# 04-multimodal-flash.net
KiCad netlist of a schematic drawn in Altium Designer
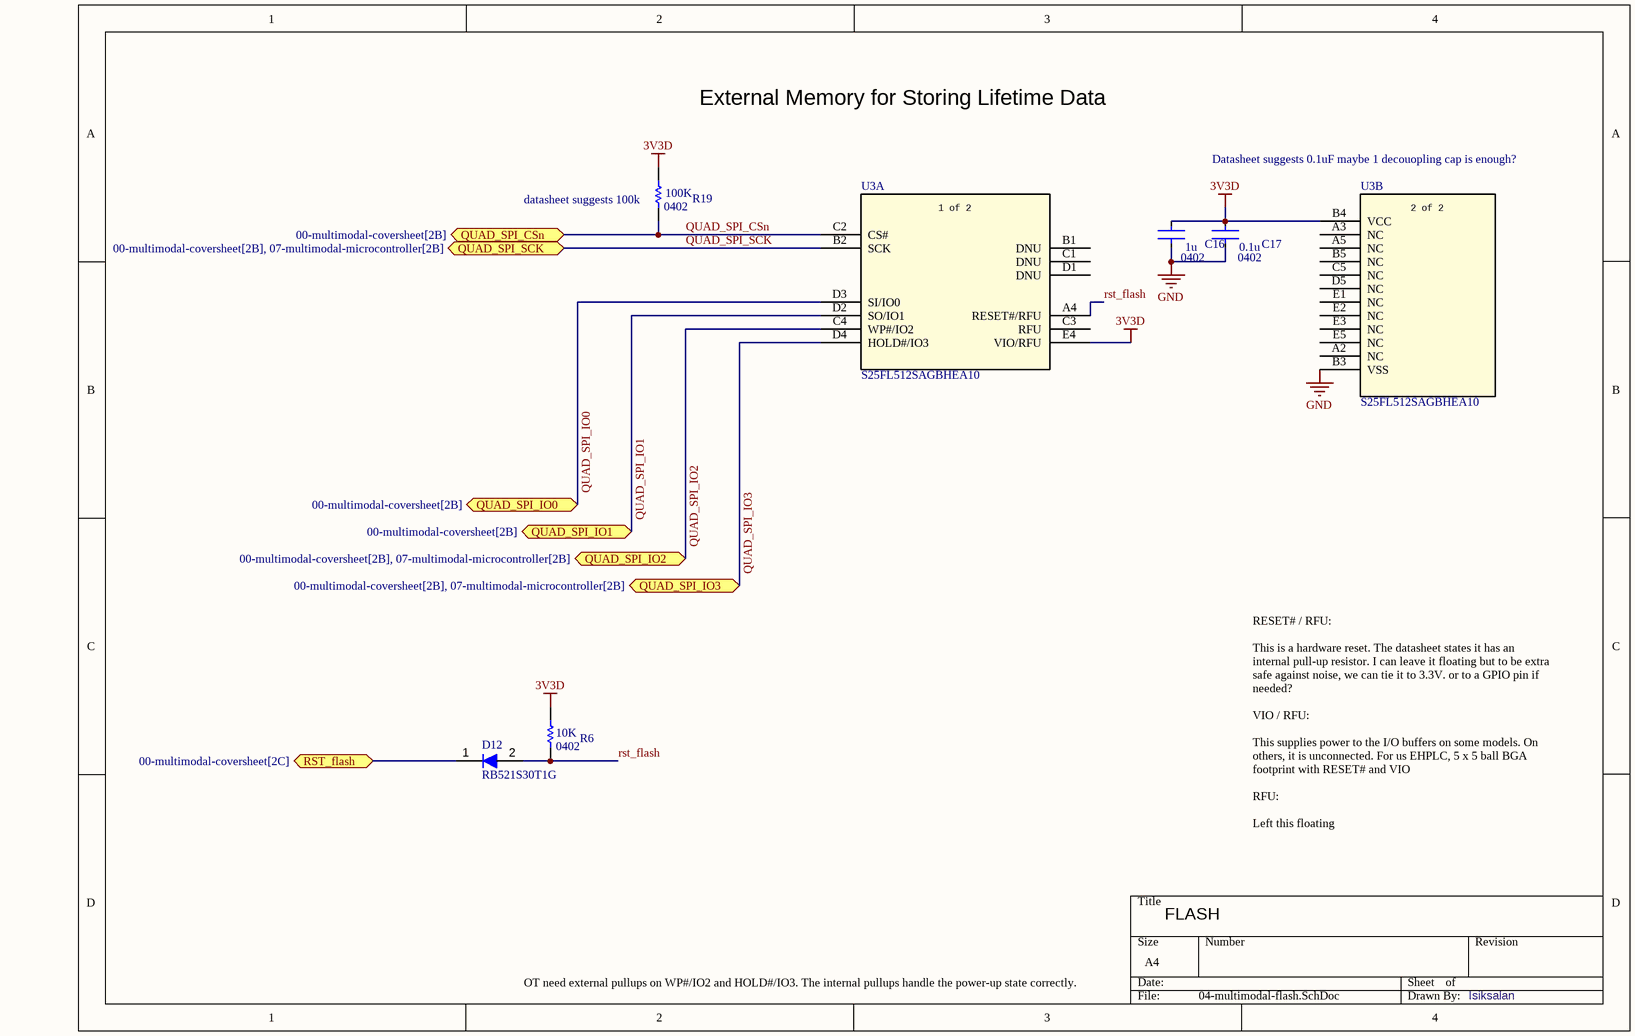
[diagram p0: 04-multimodal-flash.SchDoc]

(export (version "E")
  (design (tool "Eeschema 10.0.6"))
  (components
    (comp (ref "C16")
      (value "C1005X5R1V105K050BC")
      (footprint "CAPTDK0402")
      (description "CAP CER 1UF 35V X5R 0402")
      (libsource (lib "multimodal") (part "C1005X5R1V105K050BC"))
    )
    (comp (ref "C17")
      (value "C1005X7R1H104K050BB")
      (footprint "CAPTDK0402")
      (description "CAP CER 0.1UF 50V X7R 0402")
      (libsource (lib "multimodal") (part "C1005X7R1H104K050BB"))
    )
    (comp (ref "D12")
      (value "RB521S30T1G")
      (footprint "SOD-523_0P9X1P3_ONS-L")
      (description "DIODE SCHOTTKY 30V 200MA SOD523")
      (fields (field (name "MANUFACTURER") "Hamamatsu") (field (name "MANUFACTURER PART NUMBER") "S15193"))
      (libsource (lib "multimodal") (part "RB521S30T1G"))
    )
    (comp (ref "R6")
      (value "RMCF0402FT10K0")
      (footprint "RES-STACK-POLE-0402")
      (description "RES 10K OHM 1% 1/16W 0402")
      (libsource (lib "multimodal") (part "RMCF0402FT10K0"))
    )
    (comp (ref "R19")
      (value "RMCF0402FT100K")
      (footprint "RES-STACK-POLE-0402")
      (description "RES 100K OHM 1% 1/16W 0402")
      (libsource (lib "multimodal") (part "RMCF0402FT100K"))
    )
    (comp (ref "U3")
      (value "S25FL512SAGBHEA10")
      (footprint "BGA5x5_S25FL512SAGBHEA10_INF")
      (description "FLASH - NOR Memory IC 512Mbit SPI - Quad I/O 133 MHz 24-BGA (6x8)")
      (fields (field (name "COPYRIGHT") "Copyright (C) 2025 Ultra Librarian. All rights reserved."))
      (libsource (lib "multimodal") (part "S25FL512SAGBHEA10"))
    )
  )
  (nets
    (net (code "1") (name "/QUAD_SPI_CSn") (class "Default")
      (node (ref "R19") (pin "1") (pinfunction "1_1") (pintype "passive"))
      (node (ref "U3") (pin "C2") (pinfunction "CS#_C2") (pintype "passive"))
    )
    (net (code "2") (name "/QUAD_SPI_IO0") (class "Default")
      (node (ref "U3") (pin "D3") (pinfunction "SI/IO0_D3") (pintype "passive"))
    )
    (net (code "3") (name "/QUAD_SPI_IO1") (class "Default")
      (node (ref "U3") (pin "D2") (pinfunction "SO/IO1_D2") (pintype "passive"))
    )
    (net (code "4") (name "/QUAD_SPI_IO2") (class "Default")
      (node (ref "U3") (pin "C4") (pinfunction "WP#/IO2_C4") (pintype "passive"))
    )
    (net (code "5") (name "/QUAD_SPI_IO3") (class "Default")
      (node (ref "U3") (pin "D4") (pinfunction "HOLD#/IO3_D4") (pintype "passive"))
    )
    (net (code "6") (name "/QUAD_SPI_SCK") (class "Default")
      (node (ref "U3") (pin "B2") (pinfunction "SCK_B2") (pintype "passive"))
    )
    (net (code "7") (name "/RST_flash") (class "Default") (node (ref "D12") (pin "1") (pintype "passive")))
    (net (code "8") (name "/rst_flash") (class "Default")
      (node (ref "D12") (pin "2") (pintype "passive"))
      (node (ref "R6") (pin "1") (pinfunction "1_1") (pintype "passive"))
      (node (ref "U3") (pin "A4") (pinfunction "RESET#/RFU_A4") (pintype "passive"))
    )
    (net (code "9") (name "3V3D") (class "Default")
      (node (ref "C16") (pin "1") (pinfunction "1_1") (pintype "passive"))
      (node (ref "C17") (pin "1") (pinfunction "1_1") (pintype "passive"))
      (node (ref "R19") (pin "2") (pinfunction "2_2") (pintype "passive"))
      (node (ref "R6") (pin "2") (pinfunction "2_2") (pintype "passive"))
      (node (ref "U3") (pin "B4") (pinfunction "VCC_B4") (pintype "power_in"))
      (node (ref "U3") (pin "E4") (pinfunction "VIO/RFU_E4") (pintype "passive"))
    )
    (net (code "10") (name "GND") (class "Default")
      (node (ref "C16") (pin "2") (pinfunction "2_2") (pintype "passive"))
      (node (ref "C17") (pin "2") (pinfunction "2_2") (pintype "passive"))
      (node (ref "U3") (pin "B3") (pinfunction "VSS_B3") (pintype "power_in"))
    )
    (net (code "11") (name "unconnected-(U3A-DNU-PadB1)") (class "Default")
      (node (ref "U3") (pin "B1") (pinfunction "DNU_B1") (pintype "passive"))
    )
    (net (code "12") (name "unconnected-(U3A-DNU-PadC1)") (class "Default")
      (node (ref "U3") (pin "C1") (pinfunction "DNU_C1") (pintype "passive"))
    )
    (net (code "13") (name "unconnected-(U3A-DNU-PadD1)") (class "Default")
      (node (ref "U3") (pin "D1") (pinfunction "DNU_D1") (pintype "passive"))
    )
    (net (code "14") (name "unconnected-(U3A-RFU-PadC3)") (class "Default")
      (node (ref "U3") (pin "C3") (pinfunction "RFU_C3") (pintype "passive"))
    )
    (net (code "15") (name "unconnected-(U3B-NC-PadA2)") (class "Default")
      (node (ref "U3") (pin "A2") (pinfunction "NC_A2") (pintype "passive"))
    )
    (net (code "16") (name "unconnected-(U3B-NC-PadA3)") (class "Default")
      (node (ref "U3") (pin "A3") (pinfunction "NC_A3") (pintype "passive"))
    )
    (net (code "17") (name "unconnected-(U3B-NC-PadA5)") (class "Default")
      (node (ref "U3") (pin "A5") (pinfunction "NC_A5") (pintype "passive"))
    )
    (net (code "18") (name "unconnected-(U3B-NC-PadB5)") (class "Default")
      (node (ref "U3") (pin "B5") (pinfunction "NC_B5") (pintype "passive"))
    )
    (net (code "19") (name "unconnected-(U3B-NC-PadC5)") (class "Default")
      (node (ref "U3") (pin "C5") (pinfunction "NC_C5") (pintype "passive"))
    )
    (net (code "20") (name "unconnected-(U3B-NC-PadD5)") (class "Default")
      (node (ref "U3") (pin "D5") (pinfunction "NC_D5") (pintype "passive"))
    )
    (net (code "21") (name "unconnected-(U3B-NC-PadE1)") (class "Default")
      (node (ref "U3") (pin "E1") (pinfunction "NC_E1") (pintype "passive"))
    )
    (net (code "22") (name "unconnected-(U3B-NC-PadE2)") (class "Default")
      (node (ref "U3") (pin "E2") (pinfunction "NC_E2") (pintype "passive"))
    )
    (net (code "23") (name "unconnected-(U3B-NC-PadE3)") (class "Default")
      (node (ref "U3") (pin "E3") (pinfunction "NC_E3") (pintype "passive"))
    )
    (net (code "24") (name "unconnected-(U3B-NC-PadE5)") (class "Default")
      (node (ref "U3") (pin "E5") (pinfunction "NC_E5") (pintype "passive"))
    )
  )
)
